# SoundLab.net
KiCad netlist of a schematic drawn in EAGLE
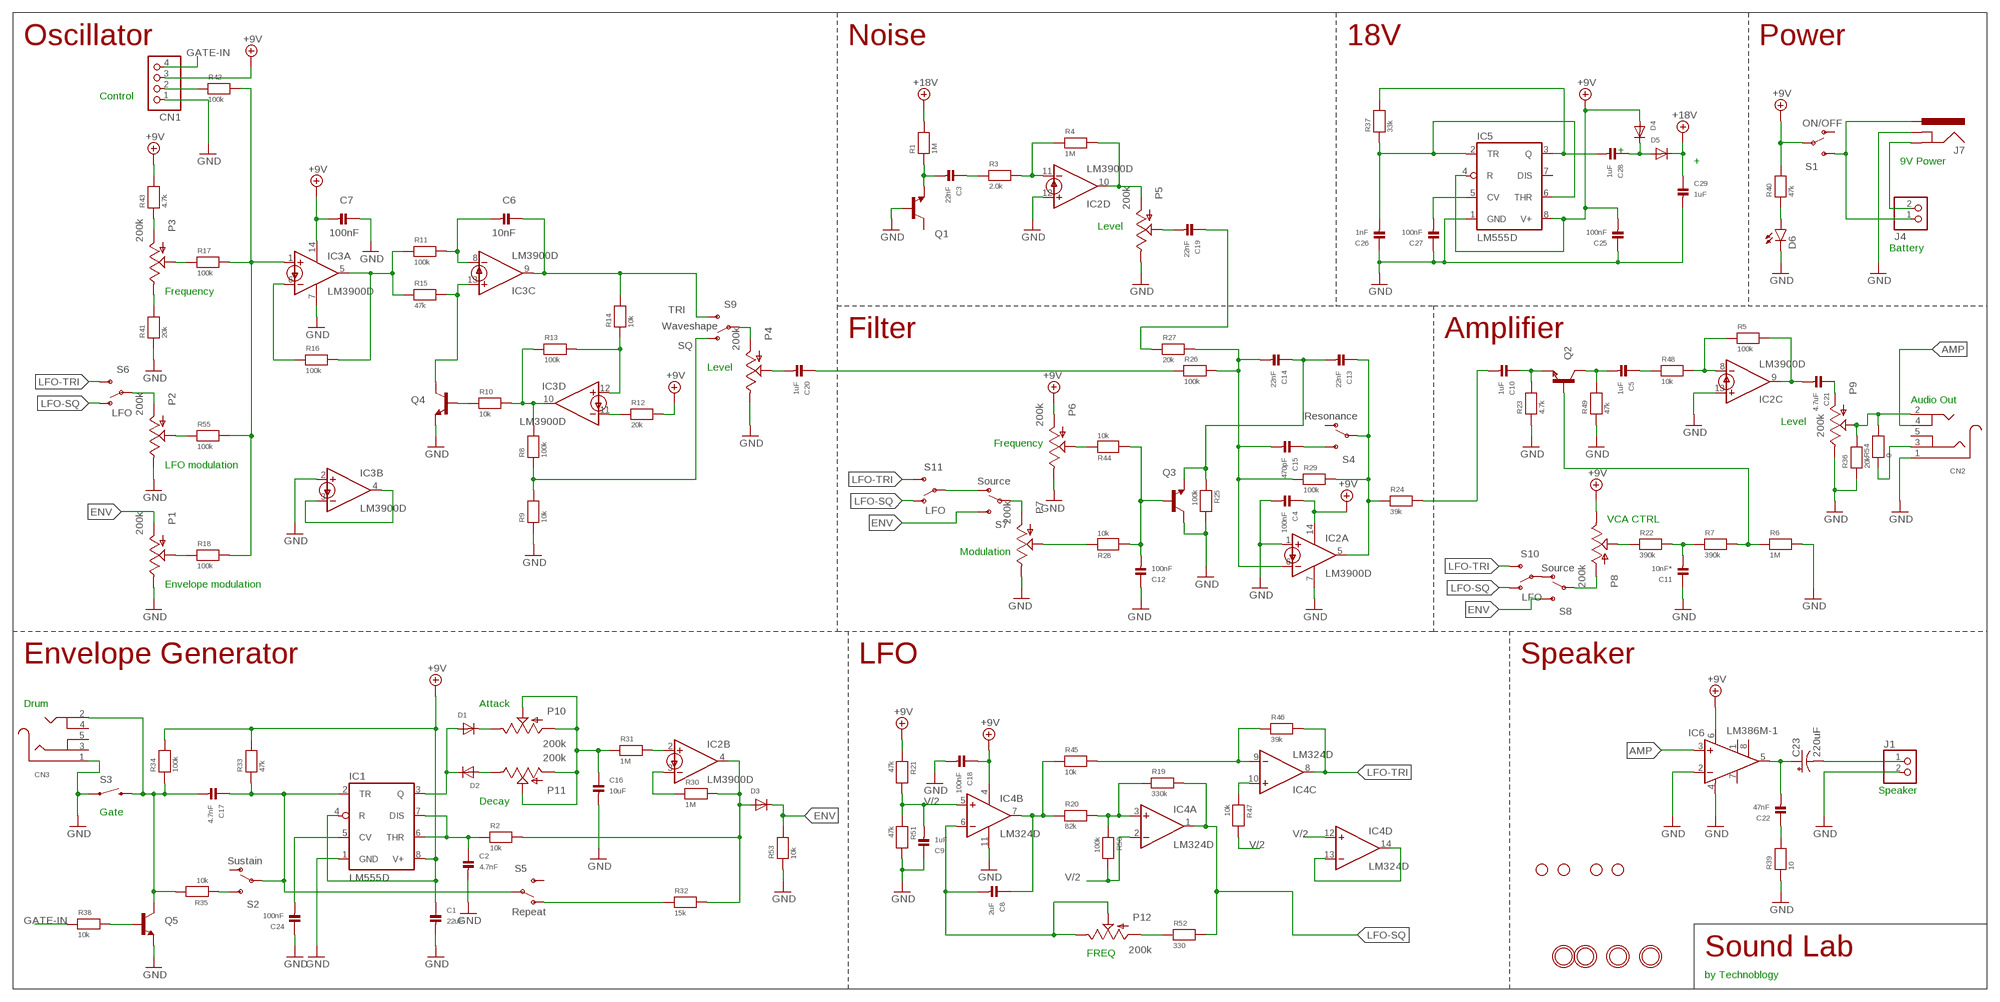
[diagram p0: schematic, sheet 1]

(export (version "E")
  (design (tool "Eeschema 10.0.6"))
  (components
    (comp (ref "C1")
      (value "22uF")
      (footprint "eagle-import:_0805MP")
      (libsource (lib "eagle-import") (part "CAP_CERAMIC_0805MP"))
    )
    (comp (ref "C2")
      (value "4.7nF")
      (footprint "eagle-import:_0805MP")
      (libsource (lib "eagle-import") (part "CAP_CERAMIC_0805MP"))
    )
    (comp (ref "C3")
      (value "22nF")
      (footprint "eagle-import:_0805MP")
      (libsource (lib "eagle-import") (part "CAP_CERAMIC_0805MP"))
    )
    (comp (ref "C4")
      (value "100nF")
      (footprint "eagle-import:_0805MP")
      (libsource (lib "eagle-import") (part "CAP_CERAMIC_0805MP"))
    )
    (comp (ref "C5")
      (value "1uF")
      (footprint "eagle-import:_0805MP")
      (libsource (lib "eagle-import") (part "CAP_CERAMIC_0805MP"))
    )
    (comp (ref "C6")
      (value "10nF")
      (footprint "eagle-import:_0805MP")
      (libsource (lib "eagle-import") (part "CAP_CERAMIC_0805MP"))
    )
    (comp (ref "C7")
      (value "100nF")
      (footprint "eagle-import:_0805MP")
      (libsource (lib "eagle-import") (part "CAP_CERAMIC_0805MP"))
    )
    (comp (ref "C8")
      (value "2uF")
      (footprint "eagle-import:_0805MP")
      (libsource (lib "eagle-import") (part "CAP_CERAMIC_0805MP"))
    )
    (comp (ref "C9")
      (value "1uF")
      (footprint "eagle-import:_0805MP")
      (libsource (lib "eagle-import") (part "CAP_CERAMIC_0805MP"))
    )
    (comp (ref "C10")
      (value "1uF")
      (footprint "eagle-import:_0805MP")
      (libsource (lib "eagle-import") (part "CAP_CERAMIC_0805MP"))
    )
    (comp (ref "C11")
      (value "10nF*")
      (footprint "eagle-import:_0805MP")
      (libsource (lib "eagle-import") (part "CAP_CERAMIC_0805MP"))
    )
    (comp (ref "C12")
      (value "100nF")
      (footprint "eagle-import:_0805MP")
      (libsource (lib "eagle-import") (part "CAP_CERAMIC_0805MP"))
    )
    (comp (ref "C13")
      (value "22nF")
      (footprint "eagle-import:_0805MP")
      (libsource (lib "eagle-import") (part "CAP_CERAMIC_0805MP"))
    )
    (comp (ref "C14")
      (value "22nF")
      (footprint "eagle-import:_0805MP")
      (libsource (lib "eagle-import") (part "CAP_CERAMIC_0805MP"))
    )
    (comp (ref "C15")
      (value "470pF")
      (footprint "eagle-import:_0805MP")
      (libsource (lib "eagle-import") (part "CAP_CERAMIC_0805MP"))
    )
    (comp (ref "C16")
      (value "10uF")
      (footprint "eagle-import:_0805MP")
      (libsource (lib "eagle-import") (part "CAP_CERAMIC_0805MP"))
    )
    (comp (ref "C17")
      (value "4.7nF")
      (footprint "eagle-import:_0805MP")
      (libsource (lib "eagle-import") (part "CAP_CERAMIC_0805MP"))
    )
    (comp (ref "C18")
      (value "100nF")
      (footprint "eagle-import:_0805MP")
      (libsource (lib "eagle-import") (part "CAP_CERAMIC_0805MP"))
    )
    (comp (ref "C19")
      (value "22nF")
      (footprint "eagle-import:_0805MP")
      (libsource (lib "eagle-import") (part "CAP_CERAMIC_0805MP"))
    )
    (comp (ref "C20")
      (value "1uF")
      (footprint "eagle-import:_0805MP")
      (libsource (lib "eagle-import") (part "CAP_CERAMIC_0805MP"))
    )
    (comp (ref "C21")
      (value "4.7uF")
      (footprint "eagle-import:_0805MP")
      (libsource (lib "eagle-import") (part "CAP_CERAMIC_0805MP"))
    )
    (comp (ref "C22")
      (value "47nF")
      (footprint "eagle-import:_0805MP")
      (libsource (lib "eagle-import") (part "CAP_CERAMIC_0805MP"))
    )
    (comp (ref "C23")
      (value "220uF")
      (footprint "eagle-import:PANASONIC_D")
      (libsource (lib "eagle-import") (part "47UF-50V-20%(ELECT)"))
    )
    (comp (ref "C24")
      (value "100nF")
      (footprint "eagle-import:_0805MP")
      (libsource (lib "eagle-import") (part "CAP_CERAMIC_0805MP"))
    )
    (comp (ref "C25")
      (value "100nF")
      (footprint "eagle-import:_0805MP")
      (libsource (lib "eagle-import") (part "CAP_CERAMIC_0805MP"))
    )
    (comp (ref "C26")
      (value "1nF")
      (footprint "eagle-import:_0805MP")
      (libsource (lib "eagle-import") (part "CAP_CERAMIC_0805MP"))
    )
    (comp (ref "C27")
      (value "100nF")
      (footprint "eagle-import:_0805MP")
      (libsource (lib "eagle-import") (part "CAP_CERAMIC_0805MP"))
    )
    (comp (ref "C28")
      (value "1uF")
      (footprint "eagle-import:_0805MP")
      (libsource (lib "eagle-import") (part "CAP_CERAMIC_0805MP"))
    )
    (comp (ref "C29")
      (value "1uF")
      (footprint "eagle-import:_0805MP")
      (libsource (lib "eagle-import") (part "CAP_CERAMIC_0805MP"))
    )
    (comp (ref "CN1")
      (value "JST_4PIN")
      (footprint "eagle-import:JSTPH4")
      (libsource (lib "eagle-import") (part "JST_4PIN"))
    )
    (comp (ref "CN2")
      (value "AUDIO_3.5MMJACK")
      (footprint "eagle-import:4UCONN_19269")
      (libsource (lib "eagle-import") (part "AUDIO_3.5MMJACK"))
    )
    (comp (ref "CN3")
      (value "AUDIO_3.5MMJACK")
      (footprint "eagle-import:4UCONN_19269")
      (libsource (lib "eagle-import") (part "AUDIO_3.5MMJACK"))
    )
    (comp (ref "D1")
      (value "DIODESOD-123")
      (footprint "eagle-import:SOD-123")
      (libsource (lib "eagle-import") (part "DIODESOD-123"))
    )
    (comp (ref "D2")
      (value "DIODESOD-123")
      (footprint "eagle-import:SOD-123")
      (libsource (lib "eagle-import") (part "DIODESOD-123"))
    )
    (comp (ref "D3")
      (value "DIODESOD-123")
      (footprint "eagle-import:SOD-123")
      (libsource (lib "eagle-import") (part "DIODESOD-123"))
    )
    (comp (ref "D4")
      (value "DIODESOD-123")
      (footprint "eagle-import:SOD-123")
      (libsource (lib "eagle-import") (part "DIODESOD-123"))
    )
    (comp (ref "D5")
      (value "DIODESOD-123")
      (footprint "eagle-import:SOD-123")
      (libsource (lib "eagle-import") (part "DIODESOD-123"))
    )
    (comp (ref "D6")
      (value "LED1206-BOTTOM")
      (footprint "eagle-import:LED-1206-BOTTOM")
      (libsource (lib "eagle-import") (part "LED1206-BOTTOM"))
    )
    (comp (ref "IC1")
      (value "LM555D")
      (footprint "eagle-import:SO08")
      (libsource (lib "eagle-import") (part "555DLM"))
    )
    (comp (ref "IC2")
      (value "LM3900D")
      (footprint "eagle-import:SO14")
      (libsource (lib "eagle-import") (part "LM3900D"))
    )
    (comp (ref "IC3")
      (value "LM3900D")
      (footprint "eagle-import:SO14")
      (libsource (lib "eagle-import") (part "LM3900D"))
    )
    (comp (ref "IC4")
      (value "LM324D")
      (footprint "eagle-import:SO14")
      (libsource (lib "eagle-import") (part "LM324D"))
    )
    (comp (ref "IC5")
      (value "LM555D")
      (footprint "eagle-import:SO08")
      (libsource (lib "eagle-import") (part "555DLM"))
    )
    (comp (ref "IC6")
      (value "LM386M-1")
      (footprint "eagle-import:SO08")
      (libsource (lib "eagle-import") (part "LM386?-M1"))
    )
    (comp (ref "J1")
      (value "HEADER-1X2EDGE")
      (footprint "eagle-import:1X02_EDGESMT")
      (libsource (lib "eagle-import") (part "HEADER-1X2EDGE"))
    )
    (comp (ref "J4")
      (value "HEADER-1X2EDGE")
      (footprint "eagle-import:1X02_EDGESMT")
      (libsource (lib "eagle-import") (part "HEADER-1X2EDGE"))
    )
    (comp (ref "J7")
      (value "5.5x2.1mm Barrel")
      (footprint "eagle-import:POWER_JACK_SMD")
      (libsource (lib "eagle-import") (part "POWER_JACKSMD"))
    )
    (comp (ref "JP1")
      (value "STAND-OFF")
      (footprint "eagle-import:STAND-OFF")
      (libsource (lib "eagle-import") (part "STAND-OFF"))
    )
    (comp (ref "JP2")
      (value "STAND-OFF")
      (footprint "eagle-import:STAND-OFF")
      (libsource (lib "eagle-import") (part "STAND-OFF"))
    )
    (comp (ref "JP3")
      (value "STAND-OFF")
      (footprint "eagle-import:STAND-OFF")
      (libsource (lib "eagle-import") (part "STAND-OFF"))
    )
    (comp (ref "JP4")
      (value "STAND-OFF")
      (footprint "eagle-import:STAND-OFF")
      (libsource (lib "eagle-import") (part "STAND-OFF"))
    )
    (comp (ref "P1")
      (value "200k")
      (footprint "eagle-import:ALPS_POT")
      (libsource (lib "eagle-import") (part "POT"))
    )
    (comp (ref "P2")
      (value "200k")
      (footprint "eagle-import:ALPS_POT")
      (libsource (lib "eagle-import") (part "POT"))
    )
    (comp (ref "P3")
      (value "200k")
      (footprint "eagle-import:ALPS_POT")
      (libsource (lib "eagle-import") (part "POT"))
    )
    (comp (ref "P4")
      (value "200k")
      (footprint "eagle-import:ALPS_POT")
      (libsource (lib "eagle-import") (part "POT"))
    )
    (comp (ref "P5")
      (value "200k")
      (footprint "eagle-import:ALPS_POT")
      (libsource (lib "eagle-import") (part "POT"))
    )
    (comp (ref "P6")
      (value "200k")
      (footprint "eagle-import:ALPS_POT")
      (libsource (lib "eagle-import") (part "POT"))
    )
    (comp (ref "P7")
      (value "200k")
      (footprint "eagle-import:ALPS_POT")
      (libsource (lib "eagle-import") (part "POT"))
    )
    (comp (ref "P8")
      (value "200k")
      (footprint "eagle-import:ALPS_POT")
      (libsource (lib "eagle-import") (part "POT"))
    )
    (comp (ref "P9")
      (value "200k")
      (footprint "eagle-import:ALPS_POT")
      (libsource (lib "eagle-import") (part "POT"))
    )
    (comp (ref "P10")
      (value "200k")
      (footprint "eagle-import:ALPS_POT")
      (libsource (lib "eagle-import") (part "POT"))
    )
    (comp (ref "P11")
      (value "200k")
      (footprint "eagle-import:ALPS_POT")
      (libsource (lib "eagle-import") (part "POT"))
    )
    (comp (ref "P12")
      (value "200k")
      (footprint "eagle-import:ALPS_POT")
      (libsource (lib "eagle-import") (part "POT"))
    )
    (comp (ref "Q1")
      (value "MMBT3904")
      (footprint "eagle-import:SOT23-3")
      (libsource (lib "eagle-import") (part "TRANSISTOR_NPNMMBT2222A"))
    )
    (comp (ref "Q2")
      (value "MMBT3904")
      (footprint "eagle-import:SOT23-3")
      (libsource (lib "eagle-import") (part "TRANSISTOR_NPNMMBT2222A"))
    )
    (comp (ref "Q3")
      (value "MMBT3904")
      (footprint "eagle-import:SOT23-3")
      (libsource (lib "eagle-import") (part "TRANSISTOR_NPNMMBT2222A"))
    )
    (comp (ref "Q4")
      (value "MMBT3904")
      (footprint "eagle-import:SOT23-3")
      (libsource (lib "eagle-import") (part "TRANSISTOR_NPNMMBT2222A"))
    )
    (comp (ref "Q5")
      (value "MMBT3904")
      (footprint "eagle-import:SOT23-3")
      (libsource (lib "eagle-import") (part "TRANSISTOR_NPNMMBT2222A"))
    )
    (comp (ref "R1")
      (value "1M")
      (footprint "eagle-import:_0805MP")
      (libsource (lib "eagle-import") (part "RESISTOR_0805MP"))
    )
    (comp (ref "R2")
      (value "10k")
      (footprint "eagle-import:_0805MP")
      (libsource (lib "eagle-import") (part "RESISTOR_0805MP"))
    )
    (comp (ref "R3")
      (value "2.0k")
      (footprint "eagle-import:_0805MP")
      (libsource (lib "eagle-import") (part "RESISTOR_0805MP"))
    )
    (comp (ref "R4")
      (value "1M")
      (footprint "eagle-import:_0805MP")
      (libsource (lib "eagle-import") (part "RESISTOR_0805MP"))
    )
    (comp (ref "R5")
      (value "100k")
      (footprint "eagle-import:_0805MP")
      (libsource (lib "eagle-import") (part "RESISTOR_0805MP"))
    )
    (comp (ref "R6")
      (value "1M")
      (footprint "eagle-import:_0805MP")
      (libsource (lib "eagle-import") (part "RESISTOR_0805MP"))
    )
    (comp (ref "R7")
      (value "390k")
      (footprint "eagle-import:_0805MP")
      (libsource (lib "eagle-import") (part "RESISTOR_0805MP"))
    )
    (comp (ref "R8")
      (value "100k")
      (footprint "eagle-import:_0805MP")
      (libsource (lib "eagle-import") (part "RESISTOR_0805MP"))
    )
    (comp (ref "R9")
      (value "10k")
      (footprint "eagle-import:_0805MP")
      (libsource (lib "eagle-import") (part "RESISTOR_0805MP"))
    )
    (comp (ref "R10")
      (value "10k")
      (footprint "eagle-import:_0805MP")
      (libsource (lib "eagle-import") (part "RESISTOR_0805MP"))
    )
    (comp (ref "R11")
      (value "100k")
      (footprint "eagle-import:_0805MP")
      (libsource (lib "eagle-import") (part "RESISTOR_0805MP"))
    )
    (comp (ref "R12")
      (value "20k")
      (footprint "eagle-import:_0805MP")
      (libsource (lib "eagle-import") (part "RESISTOR_0805MP"))
    )
    (comp (ref "R13")
      (value "100k")
      (footprint "eagle-import:_0805MP")
      (libsource (lib "eagle-import") (part "RESISTOR_0805MP"))
    )
    (comp (ref "R14")
      (value "10k")
      (footprint "eagle-import:_0805MP")
      (libsource (lib "eagle-import") (part "RESISTOR_0805MP"))
    )
    (comp (ref "R15")
      (value "47k")
      (footprint "eagle-import:_0805MP")
      (libsource (lib "eagle-import") (part "RESISTOR_0805MP"))
    )
    (comp (ref "R16")
      (value "100k")
      (footprint "eagle-import:_0805MP")
      (libsource (lib "eagle-import") (part "RESISTOR_0805MP"))
    )
    (comp (ref "R17")
      (value "100k")
      (footprint "eagle-import:_0805MP")
      (libsource (lib "eagle-import") (part "RESISTOR_0805MP"))
    )
    (comp (ref "R18")
      (value "100k")
      (footprint "eagle-import:_0805MP")
      (libsource (lib "eagle-import") (part "RESISTOR_0805MP"))
    )
    (comp (ref "R19")
      (value "330k")
      (footprint "eagle-import:_0805MP")
      (libsource (lib "eagle-import") (part "RESISTOR_0805MP"))
    )
    (comp (ref "R20")
      (value "82k")
      (footprint "eagle-import:_0805MP")
      (libsource (lib "eagle-import") (part "RESISTOR_0805MP"))
    )
    (comp (ref "R21")
      (value "47k")
      (footprint "eagle-import:_0805MP")
      (libsource (lib "eagle-import") (part "RESISTOR_0805MP"))
    )
    (comp (ref "R22")
      (value "390k")
      (footprint "eagle-import:_0805MP")
      (libsource (lib "eagle-import") (part "RESISTOR_0805MP"))
    )
    (comp (ref "R23")
      (value "4.7k")
      (footprint "eagle-import:_0805MP")
      (libsource (lib "eagle-import") (part "RESISTOR_0805MP"))
    )
    (comp (ref "R24")
      (value "39k")
      (footprint "eagle-import:_0805MP")
      (libsource (lib "eagle-import") (part "RESISTOR_0805MP"))
    )
    (comp (ref "R25")
      (value "100k")
      (footprint "eagle-import:_0805MP")
      (libsource (lib "eagle-import") (part "RESISTOR_0805MP"))
    )
    (comp (ref "R26")
      (value "100k")
      (footprint "eagle-import:_0805MP")
      (libsource (lib "eagle-import") (part "RESISTOR_0805MP"))
    )
    (comp (ref "R27")
      (value "20k")
      (footprint "eagle-import:_0805MP")
      (libsource (lib "eagle-import") (part "RESISTOR_0805MP"))
    )
    (comp (ref "R28")
      (value "10k")
      (footprint "eagle-import:_0805MP")
      (libsource (lib "eagle-import") (part "RESISTOR_0805MP"))
    )
    (comp (ref "R29")
      (value "100k")
      (footprint "eagle-import:_0805MP")
      (libsource (lib "eagle-import") (part "RESISTOR_0805MP"))
    )
    (comp (ref "R30")
      (value "1M")
      (footprint "eagle-import:_0805MP")
      (libsource (lib "eagle-import") (part "RESISTOR_0805MP"))
    )
    (comp (ref "R31")
      (value "1M")
      (footprint "eagle-import:_0805MP")
      (libsource (lib "eagle-import") (part "RESISTOR_0805MP"))
    )
    (comp (ref "R32")
      (value "15k")
      (footprint "eagle-import:_0805MP")
      (libsource (lib "eagle-import") (part "RESISTOR_0805MP"))
    )
    (comp (ref "R33")
      (value "47k")
      (footprint "eagle-import:_0805MP")
      (libsource (lib "eagle-import") (part "RESISTOR_0805MP"))
    )
    (comp (ref "R34")
      (value "100k")
      (footprint "eagle-import:_0805MP")
      (libsource (lib "eagle-import") (part "RESISTOR_0805MP"))
    )
    (comp (ref "R35")
      (value "10k")
      (footprint "eagle-import:_0805MP")
      (libsource (lib "eagle-import") (part "RESISTOR_0805MP"))
    )
    (comp (ref "R36")
      (value "20k")
      (footprint "eagle-import:_0805MP")
      (libsource (lib "eagle-import") (part "RESISTOR_0805MP"))
    )
    (comp (ref "R37")
      (value "33k")
      (footprint "eagle-import:_0805MP")
      (libsource (lib "eagle-import") (part "RESISTOR_0805MP"))
    )
    (comp (ref "R38")
      (value "10k")
      (footprint "eagle-import:_0805MP")
      (libsource (lib "eagle-import") (part "RESISTOR_0805MP"))
    )
    (comp (ref "R39")
      (value "10")
      (footprint "eagle-import:_0805MP")
      (libsource (lib "eagle-import") (part "RESISTOR_0805MP"))
    )
    (comp (ref "R40")
      (value "47k")
      (footprint "eagle-import:_0805MP")
      (libsource (lib "eagle-import") (part "RESISTOR_0805MP"))
    )
    (comp (ref "R41")
      (value "20k")
      (footprint "eagle-import:_0805MP")
      (libsource (lib "eagle-import") (part "RESISTOR_0805MP"))
    )
    (comp (ref "R42")
      (value "100k")
      (footprint "eagle-import:_0805MP")
      (libsource (lib "eagle-import") (part "RESISTOR_0805MP"))
    )
    (comp (ref "R43")
      (value "4.7k")
      (footprint "eagle-import:_0805MP")
      (libsource (lib "eagle-import") (part "RESISTOR_0805MP"))
    )
    (comp (ref "R44")
      (value "10k")
      (footprint "eagle-import:_0805MP")
      (libsource (lib "eagle-import") (part "RESISTOR_0805MP"))
    )
    (comp (ref "R45")
      (value "10k")
      (footprint "eagle-import:_0805MP")
      (libsource (lib "eagle-import") (part "RESISTOR_0805MP"))
    )
    (comp (ref "R46")
      (value "39k")
      (footprint "eagle-import:_0805MP")
      (libsource (lib "eagle-import") (part "RESISTOR_0805MP"))
    )
    (comp (ref "R47")
      (value "10k")
      (footprint "eagle-import:_0805MP")
      (libsource (lib "eagle-import") (part "RESISTOR_0805MP"))
    )
    (comp (ref "R48")
      (value "10k")
      (footprint "eagle-import:_0805MP")
      (libsource (lib "eagle-import") (part "RESISTOR_0805MP"))
    )
    (comp (ref "R49")
      (value "47k")
      (footprint "eagle-import:_0805MP")
      (libsource (lib "eagle-import") (part "RESISTOR_0805MP"))
    )
    (comp (ref "R50")
      (value "100k")
      (footprint "eagle-import:_0805MP")
      (libsource (lib "eagle-import") (part "RESISTOR_0805MP"))
    )
    (comp (ref "R51")
      (value "47k")
      (footprint "eagle-import:_0805MP")
      (libsource (lib "eagle-import") (part "RESISTOR_0805MP"))
    )
    (comp (ref "R52")
      (value "330")
      (footprint "eagle-import:_0805MP")
      (libsource (lib "eagle-import") (part "RESISTOR_0805MP"))
    )
    (comp (ref "R53")
      (value "10k")
      (footprint "eagle-import:_0805MP")
      (libsource (lib "eagle-import") (part "RESISTOR_0805MP"))
    )
    (comp (ref "R54")
      (value "0")
      (footprint "eagle-import:_0805MP")
      (libsource (lib "eagle-import") (part "RESISTOR_0805MP"))
    )
    (comp (ref "R55")
      (value "100k")
      (footprint "eagle-import:_0805MP")
      (libsource (lib "eagle-import") (part "RESISTOR_0805MP"))
    )
    (comp (ref "S1")
      (value "ON/OFF")
      (footprint "eagle-import:SWITCH-SPDT")
      (libsource (lib "eagle-import") (part "SWITCH-SPDTPTH"))
    )
    (comp (ref "S2")
      (value "Sustain")
      (footprint "eagle-import:SWITCH-SPDT")
      (libsource (lib "eagle-import") (part "SWITCH-SPDTPTH"))
    )
    (comp (ref "S3")
      (value "SWITCH-MOMENTARY-212MM")
      (footprint "eagle-import:TACTILE-PTH-12MM")
      (libsource (lib "eagle-import") (part "SWITCH-MOMENTARY-212MM"))
    )
    (comp (ref "S4")
      (value "Resonance")
      (footprint "eagle-import:SWITCH-SPDT")
      (libsource (lib "eagle-import") (part "SWITCH-SPDTPTH"))
    )
    (comp (ref "S5")
      (value "Repeat")
      (footprint "eagle-import:SWITCH-SPDT")
      (libsource (lib "eagle-import") (part "SWITCH-SPDTPTH"))
    )
    (comp (ref "S6")
      (value "LFO")
      (footprint "eagle-import:SWITCH-SPDT")
      (libsource (lib "eagle-import") (part "SWITCH-SPDTPTH"))
    )
    (comp (ref "S7")
      (value "Source")
      (footprint "eagle-import:SWITCH-SPDT")
      (libsource (lib "eagle-import") (part "SWITCH-SPDTPTH"))
    )
    (comp (ref "S8")
      (value "Source")
      (footprint "eagle-import:SWITCH-SPDT")
      (libsource (lib "eagle-import") (part "SWITCH-SPDTPTH"))
    )
    (comp (ref "S9")
      (value "Waveshape")
      (footprint "eagle-import:SWITCH-SPDT")
      (libsource (lib "eagle-import") (part "SWITCH-SPDTPTH"))
    )
    (comp (ref "S10")
      (value "LFO")
      (footprint "eagle-import:SWITCH-SPDT")
      (libsource (lib "eagle-import") (part "SWITCH-SPDTPTH"))
    )
    (comp (ref "S11")
      (value "LFO")
      (footprint "eagle-import:SWITCH-SPDT")
      (libsource (lib "eagle-import") (part "SWITCH-SPDTPTH"))
    )
    (comp (ref "U$2")
      (value "MOUNTINGHOLE2.0")
      (footprint "eagle-import:MOUNTINGHOLE_2.0_PLATED")
      (libsource (lib "eagle-import") (part "MOUNTINGHOLE2.0"))
    )
    (comp (ref "U$3")
      (value "MOUNTINGHOLE2.0")
      (footprint "eagle-import:MOUNTINGHOLE_2.0_PLATED")
      (libsource (lib "eagle-import") (part "MOUNTINGHOLE2.0"))
    )
    (comp (ref "U$6")
      (value "MOUNTINGHOLE2.0")
      (footprint "eagle-import:MOUNTINGHOLE_2.0_PLATED")
      (libsource (lib "eagle-import") (part "MOUNTINGHOLE2.0"))
    )
    (comp (ref "U$7")
      (value "MOUNTINGHOLE2.0")
      (footprint "eagle-import:MOUNTINGHOLE_2.0_PLATED")
      (libsource (lib "eagle-import") (part "MOUNTINGHOLE2.0"))
    )
  )
  (nets
    (net (code "1") (name "+9V") (class "Default")
      (node (ref "C1") (pin "1") (pinfunction "P$1_1") (pintype "passive"))
      (node (ref "C18") (pin "1") (pinfunction "P$1_1") (pintype "passive"))
      (node (ref "C25") (pin "2") (pinfunction "P$2_2") (pintype "passive"))
      (node (ref "C4") (pin "1") (pinfunction "P$1_1") (pintype "passive"))
      (node (ref "C7") (pin "2") (pinfunction "P$2_2") (pintype "passive"))
      (node (ref "CN1") (pin "3") (pinfunction "3_3") (pintype "passive"))
      (node (ref "D4") (pin "A") (pinfunction "A_A") (pintype "passive"))
      (node (ref "IC1") (pin "4") (pinfunction "R_4") (pintype "input"))
      (node (ref "IC1") (pin "8") (pinfunction "V+_8") (pintype "power_in"))
      (node (ref "IC2") (pin "14") (pinfunction "V+_14") (pintype "power_in"))
      (node (ref "IC3") (pin "14") (pinfunction "V+_14") (pintype "power_in"))
      (node (ref "IC4") (pin "4") (pinfunction "V+_4") (pintype "power_in"))
      (node (ref "IC5") (pin "4") (pinfunction "R_4") (pintype "input"))
      (node (ref "IC5") (pin "8") (pinfunction "V+_8") (pintype "power_in"))
      (node (ref "IC6") (pin "6") (pinfunction "VS_6") (pintype "power_in"))
      (node (ref "P6") (pin "P$3") (pinfunction "A_P$3") (pintype "passive"))
      (node (ref "P8") (pin "P$1") (pinfunction "E_P$1") (pintype "passive"))
      (node (ref "R12") (pin "2") (pinfunction "2_2") (pintype "passive"))
      (node (ref "R21") (pin "1") (pinfunction "1_1") (pintype "passive"))
      (node (ref "R33") (pin "2") (pinfunction "2_2") (pintype "passive"))
      (node (ref "R34") (pin "2") (pinfunction "2_2") (pintype "passive"))
      (node (ref "R40") (pin "2") (pinfunction "2_2") (pintype "passive"))
      (node (ref "R43") (pin "2") (pinfunction "2_2") (pintype "passive"))
      (node (ref "S1") (pin "2") (pinfunction "P_2") (pintype "passive"))
    )
    (net (code "2") (name "+18V") (class "Default")
      (node (ref "C29") (pin "1") (pinfunction "P$1_1") (pintype "passive"))
      (node (ref "D5") (pin "C") (pinfunction "C_C") (pintype "passive"))
      (node (ref "R1") (pin "2") (pinfunction "2_2") (pintype "passive"))
    )
    (net (code "3") (name "/GATE-IN") (class "Default")
      (node (ref "CN1") (pin "4") (pinfunction "4_4") (pintype "passive"))
      (node (ref "R38") (pin "1") (pinfunction "1_1") (pintype "passive"))
    )
    (net (code "4") (name "/SQ") (class "Default")
      (node (ref "R8") (pin "1") (pinfunction "1_1") (pintype "passive"))
      (node (ref "R9") (pin "2") (pinfunction "2_2") (pintype "passive"))
      (node (ref "S9") (pin "1") (pinfunction "O_1") (pintype "passive"))
    )
    (net (code "5") (name "/TRI") (class "Default")
      (node (ref "C6") (pin "1") (pinfunction "P$1_1") (pintype "passive"))
      (node (ref "IC3") (pin "9") (pinfunction "OUT_9") (pintype "output"))
      (node (ref "R14") (pin "2") (pinfunction "2_2") (pintype "passive"))
      (node (ref "S9") (pin "3") (pinfunction "S_3") (pintype "passive"))
    )
    (net (code "6") (name "/V{slash}2") (class "Default")
      (node (ref "C9") (pin "2") (pinfunction "P$2_2") (pintype "passive"))
      (node (ref "IC4") (pin "12") (pinfunction "+IN_12") (pintype "input"))
      (node (ref "IC4") (pin "2") (pinfunction "-IN_2") (pintype "input"))
      (node (ref "IC4") (pin "5") (pinfunction "+IN_5") (pintype "input"))
      (node (ref "R21") (pin "2") (pinfunction "2_2") (pintype "passive"))
      (node (ref "R47") (pin "2") (pinfunction "2_2") (pintype "passive"))
      (node (ref "R50") (pin "2") (pinfunction "2_2") (pintype "passive"))
      (node (ref "R51") (pin "1") (pinfunction "1_1") (pintype "passive"))
    )
    (net (code "7") (name "AMP") (class "Default")
      (node (ref "CN2") (pin "4") (pinfunction "P$4_4") (pintype "bidirectional"))
      (node (ref "IC6") (pin "3") (pinfunction "+IN_3") (pintype "input"))
    )
    (net (code "8") (name "ENV") (class "Default")
      (node (ref "D3") (pin "C") (pinfunction "C_C") (pintype "passive"))
      (node (ref "P1") (pin "P$3") (pinfunction "A_P$3") (pintype "passive"))
      (node (ref "R53") (pin "2") (pinfunction "2_2") (pintype "passive"))
      (node (ref "S7") (pin "3") (pinfunction "S_3") (pintype "passive"))
      (node (ref "S8") (pin "3") (pinfunction "S_3") (pintype "passive"))
    )
    (net (code "9") (name "GND") (class "Default")
      (node (ref "C1") (pin "2") (pinfunction "P$2_2") (pintype "passive"))
      (node (ref "C11") (pin "1") (pinfunction "P$1_1") (pintype "passive"))
      (node (ref "C12") (pin "1") (pinfunction "P$1_1") (pintype "passive"))
      (node (ref "C16") (pin "2") (pinfunction "P$2_2") (pintype "passive"))
      (node (ref "C18") (pin "2") (pinfunction "P$2_2") (pintype "passive"))
      (node (ref "C2") (pin "2") (pinfunction "P$2_2") (pintype "passive"))
      (node (ref "C24") (pin "1") (pinfunction "P$1_1") (pintype "passive"))
      (node (ref "C25") (pin "1") (pinfunction "P$1_1") (pintype "passive"))
      (node (ref "C26") (pin "1") (pinfunction "P$1_1") (pintype "passive"))
      (node (ref "C27") (pin "1") (pinfunction "P$1_1") (pintype "passive"))
      (node (ref "C29") (pin "2") (pinfunction "P$2_2") (pintype "passive"))
      (node (ref "C4") (pin "2") (pinfunction "P$2_2") (pintype "passive"))
      (node (ref "C7") (pin "1") (pinfunction "P$1_1") (pintype "passive"))
      (node (ref "C9") (pin "1") (pinfunction "P$1_1") (pintype "passive"))
      (node (ref "CN1") (pin "1") (pinfunction "1_1") (pintype "passive"))
      (node (ref "CN2") (pin "1") (pinfunction "P$1_1") (pintype "bidirectional"))
      (node (ref "CN3") (pin "1") (pinfunction "P$1_1") (pintype "bidirectional"))
      (node (ref "D6") (pin "C") (pinfunction "C_C") (pintype "passive"))
      (node (ref "IC1") (pin "1") (pinfunction "GND_1") (pintype "power_in"))
      (node (ref "IC2") (pin "1") (pinfunction "+IN_1") (pintype "input"))
      (node (ref "IC2") (pin "12") (pinfunction "+IN_12") (pintype "input"))
      (node (ref "IC2") (pin "13") (pinfunction "+IN_13") (pintype "input"))
      (node (ref "IC2") (pin "7") (pinfunction "GND_7") (pintype "power_in"))
      (node (ref "IC3") (pin "2") (pinfunction "+IN_2") (pintype "input"))
      (node (ref "IC3") (pin "7") (pinfunction "GND_7") (pintype "power_in"))
      (node (ref "IC4") (pin "11") (pinfunction "V-_11") (pintype "power_in"))
      (node (ref "IC5") (pin "1") (pinfunction "GND_1") (pintype "power_in"))
      (node (ref "IC6") (pin "2") (pinfunction "-IN_2") (pintype "input"))
      (node (ref "IC6") (pin "4") (pinfunction "GND_4") (pintype "power_in"))
      (node (ref "J1") (pin "2") (pinfunction "2_2") (pintype "passive"))
      (node (ref "J7") (pin "GND") (pinfunction "GNDBREAK_GND") (pintype "bidirectional"))
      (node (ref "P1") (pin "P$1") (pinfunction "E_P$1") (pintype "passive"))
      (node (ref "P2") (pin "P$1") (pinfunction "E_P$1") (pintype "passive"))
      (node (ref "P4") (pin "P$1") (pinfunction "E_P$1") (pintype "passive"))
      (node (ref "P5") (pin "P$1") (pinfunction "E_P$1") (pintype "passive"))
      (node (ref "P6") (pin "P$1") (pinfunction "E_P$1") (pintype "passive"))
      (node (ref "P7") (pin "P$1") (pinfunction "E_P$1") (pintype "passive"))
      (node (ref "P9") (pin "P$1") (pinfunction "E_P$1") (pintype "passive"))
      (node (ref "Q1") (pin "1") (pinfunction "B_1") (pintype "passive"))
      (node (ref "Q3") (pin "3") (pinfunction "C_3") (pintype "passive"))
      (node (ref "Q4") (pin "2") (pinfunction "E_2") (pintype "passive"))
      (node (ref "Q5") (pin "2") (pinfunction "E_2") (pintype "passive"))
      (node (ref "R23") (pin "1") (pinfunction "1_1") (pintype "passive"))
      (node (ref "R25") (pin "2") (pinfunction "2_2") (pintype "passive"))
      (node (ref "R36") (pin "1") (pinfunction "1_1") (pintype "passive"))
      (node (ref "R39") (pin "1") (pinfunction "1_1") (pintype "passive"))
      (node (ref "R41") (pin "1") (pinfunction "1_1") (pintype "passive"))
      (node (ref "R49") (pin "1") (pinfunction "1_1") (pintype "passive"))
      (node (ref "R51") (pin "2") (pinfunction "2_2") (pintype "passive"))
      (node (ref "R53") (pin "1") (pinfunction "1_1") (pintype "passive"))
      (node (ref "R6") (pin "2") (pinfunction "2_2") (pintype "passive"))
      (node (ref "R9") (pin "1") (pinfunction "1_1") (pintype "passive"))
      (node (ref "S3") (pin "1") (pinfunction "1_1") (pintype "passive"))
    )
    (net (code "10") (name "LFO-SQ") (class "Default")
      (node (ref "IC4") (pin "1") (pinfunction "OUT_1") (pintype "output"))
      (node (ref "R19") (pin "2") (pinfunction "2_2") (pintype "passive"))
      (node (ref "R52") (pin "2") (pinfunction "2_2") (pintype "passive"))
      (node (ref "S10") (pin "1") (pinfunction "O_1") (pintype "passive"))
      (node (ref "S11") (pin "1") (pinfunction "O_1") (pintype "passive"))
      (node (ref "S6") (pin "1") (pinfunction "O_1") (pintype "passive"))
    )
    (net (code "11") (name "LFO-TRI") (class "Default")
      (node (ref "IC4") (pin "8") (pinfunction "OUT_8") (pintype "output"))
      (node (ref "R46") (pin "2") (pinfunction "2_2") (pintype "passive"))
      (node (ref "S10") (pin "3") (pinfunction "S_3") (pintype "passive"))
      (node (ref "S11") (pin "3") (pinfunction "S_3") (pintype "passive"))
      (node (ref "S6") (pin "3") (pinfunction "S_3") (pintype "passive"))
    )
    (net (code "12") (name "Net-(C2-P$1)") (class "Default")
      (node (ref "C2") (pin "1") (pinfunction "P$1_1") (pintype "passive"))
      (node (ref "IC1") (pin "6") (pinfunction "THR_6") (pintype "input"))
      (node (ref "IC1") (pin "7") (pinfunction "DIS_7") (pintype "input"))
      (node (ref "R2") (pin "1") (pinfunction "1_1") (pintype "passive"))
    )
    (net (code "13") (name "Net-(C3-P$1)") (class "Default")
      (node (ref "C3") (pin "1") (pinfunction "P$1_1") (pintype "passive"))
      (node (ref "R3") (pin "1") (pinfunction "1_1") (pintype "passive"))
    )
    (net (code "14") (name "Net-(C3-P$2)") (class "Default")
      (node (ref "C3") (pin "2") (pinfunction "P$2_2") (pintype "passive"))
      (node (ref "Q1") (pin "2") (pinfunction "E_2") (pintype "passive"))
      (node (ref "R1") (pin "1") (pinfunction "1_1") (pintype "passive"))
    )
    (net (code "15") (name "Net-(C5-P$1)") (class "Default")
      (node (ref "C5") (pin "1") (pinfunction "P$1_1") (pintype "passive"))
      (node (ref "R48") (pin "1") (pinfunction "1_1") (pintype "passive"))
    )
    (net (code "16") (name "Net-(C5-P$2)") (class "Default")
      (node (ref "C5") (pin "2") (pinfunction "P$2_2") (pintype "passive"))
      (node (ref "Q2") (pin "3") (pinfunction "C_3") (pintype "passive"))
      (node (ref "R49") (pin "2") (pinfunction "2_2") (pintype "passive"))
    )
    (net (code "17") (name "Net-(C6-P$2)") (class "Default")
      (node (ref "C6") (pin "2") (pinfunction "P$2_2") (pintype "passive"))
      (node (ref "IC3") (pin "8") (pinfunction "-IN_8") (pintype "input"))
      (node (ref "R11") (pin "2") (pinfunction "2_2") (pintype "passive"))
    )
    (net (code "18") (name "Net-(C8-P$1)") (class "Default")
      (node (ref "C8") (pin "1") (pinfunction "P$1_1") (pintype "passive"))
      (node (ref "IC4") (pin "7") (pinfunction "OUT_7") (pintype "output"))
      (node (ref "R20") (pin "1") (pinfunction "1_1") (pintype "passive"))
      (node (ref "R45") (pin "1") (pinfunction "1_1") (pintype "passive"))
    )
    (net (code "19") (name "Net-(C8-P$2)") (class "Default")
      (node (ref "C8") (pin "2") (pinfunction "P$2_2") (pintype "passive"))
      (node (ref "IC4") (pin "6") (pinfunction "-IN_6") (pintype "input"))
      (node (ref "P12") (pin "P$1") (pinfunction "E_P$1") (pintype "passive"))
      (node (ref "P12") (pin "P$2") (pinfunction "S_P$2") (pintype "passive"))
    )
    (net (code "20") (name "Net-(C10-P$1)") (class "Default")
      (node (ref "C10") (pin "1") (pinfunction "P$1_1") (pintype "passive"))
      (node (ref "Q2") (pin "2") (pinfunction "E_2") (pintype "passive"))
      (node (ref "R23") (pin "2") (pinfunction "2_2") (pintype "passive"))
    )
    (net (code "21") (name "Net-(C10-P$2)") (class "Default")
      (node (ref "C10") (pin "2") (pinfunction "P$2_2") (pintype "passive"))
      (node (ref "R24") (pin "2") (pinfunction "2_2") (pintype "passive"))
    )
    (net (code "22") (name "Net-(C11-P$2)") (class "Default")
      (node (ref "C11") (pin "2") (pinfunction "P$2_2") (pintype "passive"))
      (node (ref "R22") (pin "2") (pinfunction "2_2") (pintype "passive"))
      (node (ref "R7") (pin "1") (pinfunction "1_1") (pintype "passive"))
    )
    (net (code "23") (name "Net-(C12-P$2)") (class "Default")
      (node (ref "C12") (pin "2") (pinfunction "P$2_2") (pintype "passive"))
      (node (ref "Q3") (pin "1") (pinfunction "B_1") (pintype "passive"))
      (node (ref "R28") (pin "2") (pinfunction "2_2") (pintype "passive"))
      (node (ref "R44") (pin "2") (pinfunction "2_2") (pintype "passive"))
    )
    (net (code "24") (name "Net-(C13-P$1)") (class "Default")
      (node (ref "C13") (pin "1") (pinfunction "P$1_1") (pintype "passive"))
      (node (ref "IC2") (pin "5") (pinfunction "OUT_5") (pintype "output"))
      (node (ref "R24") (pin "1") (pinfunction "1_1") (pintype "passive"))
      (node (ref "R29") (pin "2") (pinfunction "2_2") (pintype "passive"))
      (node (ref "S4") (pin "2") (pinfunction "P_2") (pintype "passive"))
    )
    (net (code "25") (name "Net-(C13-P$2)") (class "Default")
      (node (ref "C13") (pin "2") (pinfunction "P$2_2") (pintype "passive"))
      (node (ref "C14") (pin "1") (pinfunction "P$1_1") (pintype "passive"))
      (node (ref "Q3") (pin "2") (pinfunction "E_2") (pintype "passive"))
      (node (ref "R25") (pin "1") (pinfunction "1_1") (pintype "passive"))
    )
    (net (code "26") (name "Net-(C14-P$2)") (class "Default")
      (node (ref "C14") (pin "2") (pinfunction "P$2_2") (pintype "passive"))
      (node (ref "C15") (pin "2") (pinfunction "P$2_2") (pintype "passive"))
      (node (ref "IC2") (pin "6") (pinfunction "-IN_6") (pintype "input"))
      (node (ref "R26") (pin "2") (pinfunction "2_2") (pintype "passive"))
      (node (ref "R27") (pin "2") (pinfunction "2_2") (pintype "passive"))
      (node (ref "R29") (pin "1") (pinfunction "1_1") (pintype "passive"))
    )
    (net (code "27") (name "Net-(C15-P$1)") (class "Default")
      (node (ref "C15") (pin "1") (pinfunction "P$1_1") (pintype "passive"))
      (node (ref "S4") (pin "3") (pinfunction "S_3") (pintype "passive"))
    )
    (net (code "28") (name "Net-(C16-P$1)") (class "Default")
      (node (ref "C16") (pin "1") (pinfunction "P$1_1") (pintype "passive"))
      (node (ref "P10") (pin "P$2") (pinfunction "S_P$2") (pintype "passive"))
      (node (ref "P10") (pin "P$3") (pinfunction "A_P$3") (pintype "passive"))
      (node (ref "P11") (pin "P$2") (pinfunction "S_P$2") (pintype "passive"))
      (node (ref "P11") (pin "P$3") (pinfunction "A_P$3") (pintype "passive"))
      (node (ref "R31") (pin "1") (pinfunction "1_1") (pintype "passive"))
    )
    (net (code "29") (name "Net-(C17-P$1)") (class "Default")
      (node (ref "C17") (pin "1") (pinfunction "P$1_1") (pintype "passive"))
      (node (ref "IC1") (pin "2") (pinfunction "TR_2") (pintype "input"))
      (node (ref "R33") (pin "1") (pinfunction "1_1") (pintype "passive"))
      (node (ref "S2") (pin "2") (pinfunction "P_2") (pintype "passive"))
      (node (ref "S5") (pin "2") (pinfunction "P_2") (pintype "passive"))
    )
    (net (code "30") (name "Net-(C17-P$2)") (class "Default")
      (node (ref "C17") (pin "2") (pinfunction "P$2_2") (pintype "passive"))
      (node (ref "CN3") (pin "2") (pinfunction "P$5_2") (pintype "bidirectional"))
      (node (ref "Q5") (pin "3") (pinfunction "C_3") (pintype "passive"))
      (node (ref "R34") (pin "1") (pinfunction "1_1") (pintype "passive"))
      (node (ref "R35") (pin "2") (pinfunction "2_2") (pintype "passive"))
      (node (ref "S3") (pin "3") (pinfunction "2_3") (pintype "passive"))
    )
    (net (code "31") (name "Net-(C19-P$1)") (class "Default")
      (node (ref "C19") (pin "1") (pinfunction "P$1_1") (pintype "passive"))
      (node (ref "R27") (pin "1") (pinfunction "1_1") (pintype "passive"))
    )
    (net (code "32") (name "Net-(C19-P$2)") (class "Default")
      (node (ref "C19") (pin "2") (pinfunction "P$2_2") (pintype "passive"))
      (node (ref "P5") (pin "P$2") (pinfunction "S_P$2") (pintype "passive"))
    )
    (net (code "33") (name "Net-(C20-P$1)") (class "Default")
      (node (ref "C20") (pin "1") (pinfunction "P$1_1") (pintype "passive"))
      (node (ref "R26") (pin "1") (pinfunction "1_1") (pintype "passive"))
    )
    (net (code "34") (name "Net-(C20-P$2)") (class "Default")
      (node (ref "C20") (pin "2") (pinfunction "P$2_2") (pintype "passive"))
      (node (ref "P4") (pin "P$2") (pinfunction "S_P$2") (pintype "passive"))
    )
    (net (code "35") (name "Net-(C21-P$1)") (class "Default")
      (node (ref "C21") (pin "1") (pinfunction "P$1_1") (pintype "passive"))
      (node (ref "P9") (pin "P$3") (pinfunction "A_P$3") (pintype "passive"))
    )
    (net (code "36") (name "Net-(C21-P$2)") (class "Default")
      (node (ref "C21") (pin "2") (pinfunction "P$2_2") (pintype "passive"))
      (node (ref "IC2") (pin "9") (pinfunction "OUT_9") (pintype "output"))
      (node (ref "R5") (pin "2") (pinfunction "2_2") (pintype "passive"))
    )
    (net (code "37") (name "Net-(C22-P$1)") (class "Default")
      (node (ref "C22") (pin "1") (pinfunction "P$1_1") (pintype "passive"))
      (node (ref "R39") (pin "2") (pinfunction "2_2") (pintype "passive"))
    )
    (net (code "38") (name "Net-(C22-P$2)") (class "Default")
      (node (ref "C22") (pin "2") (pinfunction "P$2_2") (pintype "passive"))
      (node (ref "C23") (pin "+") (pinfunction "+_+") (pintype "passive"))
      (node (ref "IC6") (pin "5") (pinfunction "OUT_5") (pintype "output"))
    )
    (net (code "39") (name "Net-(C23-Pad-)") (class "Default")
      (node (ref "C23") (pin "-") (pinfunction "-_-") (pintype "passive"))
      (node (ref "J1") (pin "1") (pinfunction "1_1") (pintype "passive"))
    )
    (net (code "40") (name "Net-(C24-P$2)") (class "Default")
      (node (ref "C24") (pin "2") (pinfunction "P$2_2") (pintype "passive"))
      (node (ref "IC1") (pin "5") (pinfunction "CV_5") (pintype "input"))
    )
    (net (code "41") (name "Net-(C26-P$2)") (class "Default")
      (node (ref "C26") (pin "2") (pinfunction "P$2_2") (pintype "passive"))
      (node (ref "IC5") (pin "2") (pinfunction "TR_2") (pintype "input"))
      (node (ref "IC5") (pin "6") (pinfunction "THR_6") (pintype "input"))
      (node (ref "R37") (pin "1") (pinfunction "1_1") (pintype "passive"))
    )
    (net (code "42") (name "Net-(C27-P$2)") (class "Default")
      (node (ref "C27") (pin "2") (pinfunction "P$2_2") (pintype "passive"))
      (node (ref "IC5") (pin "5") (pinfunction "CV_5") (pintype "input"))
    )
    (net (code "43") (name "Net-(C28-P$1)") (class "Default")
      (node (ref "C28") (pin "1") (pinfunction "P$1_1") (pintype "passive"))
      (node (ref "D4") (pin "C") (pinfunction "C_C") (pintype "passive"))
      (node (ref "D5") (pin "A") (pinfunction "A_A") (pintype "passive"))
    )
    (net (code "44") (name "Net-(C28-P$2)") (class "Default")
      (node (ref "C28") (pin "2") (pinfunction "P$2_2") (pintype "passive"))
      (node (ref "IC5") (pin "3") (pinfunction "Q_3") (pintype "output"))
      (node (ref "R37") (pin "2") (pinfunction "2_2") (pintype "passive"))
    )
    (net (code "45") (name "Net-(CN1-Pad2)") (class "Default")
      (node (ref "CN1") (pin "2") (pinfunction "2_2") (pintype "passive"))
      (node (ref "R42") (pin "1") (pinfunction "1_1") (pintype "passive"))
    )
    (net (code "46") (name "Net-(CN2-P$2)") (class "Default")
      (node (ref "CN2") (pin "3") (pinfunction "P$2_3") (pintype "bidirectional"))
      (node (ref "R54") (pin "1") (pinfunction "1_1") (pintype "passive"))
    )
    (net (code "47") (name "Net-(CN2-P$5)") (class "Default")
      (node (ref "CN2") (pin "2") (pinfunction "P$5_2") (pintype "bidirectional"))
      (node (ref "P9") (pin "P$2") (pinfunction "S_P$2") (pintype "passive"))
      (node (ref "R36") (pin "2") (pinfunction "2_2") (pintype "passive"))
      (node (ref "R54") (pin "2") (pinfunction "2_2") (pintype "passive"))
    )
    (net (code "48") (name "Net-(D6-PadA)") (class "Default")
      (node (ref "D6") (pin "A") (pinfunction "A_A") (pintype "passive"))
      (node (ref "R40") (pin "1") (pinfunction "1_1") (pintype "passive"))
    )
    (net (code "49") (name "Net-(IC1-Q)") (class "Default")
      (node (ref "D1") (pin "A") (pinfunction "A_A") (pintype "passive"))
      (node (ref "D2") (pin "C") (pinfunction "C_C") (pintype "passive"))
      (node (ref "IC1") (pin "3") (pinfunction "Q_3") (pintype "output"))
    )
    (net (code "50") (name "Net-(IC2B-+IN)") (class "Default")
      (node (ref "IC2") (pin "2") (pinfunction "+IN_2") (pintype "input"))
      (node (ref "R31") (pin "2") (pinfunction "2_2") (pintype "passive"))
    )
    (net (code "51") (name "Net-(IC2B--IN)") (class "Default")
      (node (ref "IC2") (pin "3") (pinfunction "-IN_3") (pintype "input"))
      (node (ref "R30") (pin "1") (pinfunction "1_1") (pintype "passive"))
    )
    (net (code "52") (name "Net-(IC2B-OUT)") (class "Default")
      (node (ref "D3") (pin "A") (pinfunction "A_A") (pintype "passive"))
      (node (ref "IC2") (pin "4") (pinfunction "OUT_4") (pintype "output"))
      (node (ref "R2") (pin "2") (pinfunction "2_2") (pintype "passive"))
      (node (ref "R30") (pin "2") (pinfunction "2_2") (pintype "passive"))
      (node (ref "R32") (pin "2") (pinfunction "2_2") (pintype "passive"))
    )
    (net (code "53") (name "Net-(IC2C--IN)") (class "Default")
      (node (ref "IC2") (pin "8") (pinfunction "-IN_8") (pintype "input"))
      (node (ref "R48") (pin "2") (pinfunction "2_2") (pintype "passive"))
      (node (ref "R5") (pin "1") (pinfunction "1_1") (pintype "passive"))
    )
    (net (code "54") (name "Net-(IC2D--IN)") (class "Default")
      (node (ref "IC2") (pin "11") (pinfunction "-IN_11") (pintype "input"))
      (node (ref "R3") (pin "2") (pinfunction "2_2") (pintype "passive"))
      (node (ref "R4") (pin "1") (pinfunction "1_1") (pintype "passive"))
    )
    (net (code "55") (name "Net-(IC2D-OUT)") (class "Default")
      (node (ref "IC2") (pin "10") (pinfunction "OUT_10") (pintype "output"))
      (node (ref "P5") (pin "P$3") (pinfunction "A_P$3") (pintype "passive"))
      (node (ref "R4") (pin "2") (pinfunction "2_2") (pintype "passive"))
    )
    (net (code "56") (name "Net-(IC3A-+IN)") (class "Default")
      (node (ref "IC3") (pin "1") (pinfunction "+IN_1") (pintype "input"))
      (node (ref "R17") (pin "2") (pinfunction "2_2") (pintype "passive"))
      (node (ref "R18") (pin "2") (pinfunction "2_2") (pintype "passive"))
      (node (ref "R42") (pin "2") (pinfunction "2_2") (pintype "passive"))
      (node (ref "R55") (pin "2") (pinfunction "2_2") (pintype "passive"))
    )
    (net (code "57") (name "Net-(IC3A--IN)") (class "Default")
      (node (ref "IC3") (pin "6") (pinfunction "-IN_6") (pintype "input"))
      (node (ref "R16") (pin "1") (pinfunction "1_1") (pintype "passive"))
    )
    (net (code "58") (name "Net-(IC3A-OUT)") (class "Default")
      (node (ref "IC3") (pin "5") (pinfunction "OUT_5") (pintype "output"))
      (node (ref "R11") (pin "1") (pinfunction "1_1") (pintype "passive"))
      (node (ref "R15") (pin "1") (pinfunction "1_1") (pintype "passive"))
      (node (ref "R16") (pin "2") (pinfunction "2_2") (pintype "passive"))
    )
    (net (code "59") (name "Net-(IC3B--IN)") (class "Default")
      (node (ref "IC3") (pin "3") (pinfunction "-IN_3") (pintype "input"))
      (node (ref "IC3") (pin "4") (pinfunction "OUT_4") (pintype "output"))
    )
    (net (code "60") (name "Net-(IC3C-+IN)") (class "Default")
      (node (ref "IC3") (pin "13") (pinfunction "+IN_13") (pintype "input"))
      (node (ref "Q4") (pin "3") (pinfunction "C_3") (pintype "passive"))
      (node (ref "R15") (pin "2") (pinfunction "2_2") (pintype "passive"))
    )
    (net (code "61") (name "Net-(IC3D-+IN)") (class "Default")
      (node (ref "IC3") (pin "12") (pinfunction "+IN_12") (pintype "input"))
      (node (ref "R13") (pin "2") (pinfunction "2_2") (pintype "passive"))
      (node (ref "R14") (pin "1") (pinfunction "1_1") (pintype "passive"))
    )
    (net (code "62") (name "Net-(IC3D--IN)") (class "Default")
      (node (ref "IC3") (pin "11") (pinfunction "-IN_11") (pintype "input"))
      (node (ref "R12") (pin "1") (pinfunction "1_1") (pintype "passive"))
    )
    (net (code "63") (name "Net-(IC3D-OUT)") (class "Default")
      (node (ref "IC3") (pin "10") (pinfunction "OUT_10") (pintype "output"))
      (node (ref "R10") (pin "2") (pinfunction "2_2") (pintype "passive"))
      (node (ref "R13") (pin "1") (pinfunction "1_1") (pintype "passive"))
      (node (ref "R8") (pin "2") (pinfunction "2_2") (pintype "passive"))
    )
    (net (code "64") (name "Net-(IC4A-+IN)") (class "Default")
      (node (ref "IC4") (pin "3") (pinfunction "+IN_3") (pintype "input"))
      (node (ref "R19") (pin "1") (pinfunction "1_1") (pintype "passive"))
      (node (ref "R20") (pin "2") (pinfunction "2_2") (pintype "passive"))
      (node (ref "R50") (pin "1") (pinfunction "1_1") (pintype "passive"))
    )
    (net (code "65") (name "Net-(IC4C-+IN)") (class "Default")
      (node (ref "IC4") (pin "10") (pinfunction "+IN_10") (pintype "input"))
      (node (ref "R47") (pin "1") (pinfunction "1_1") (pintype "passive"))
    )
    (net (code "66") (name "Net-(IC4C--IN)") (class "Default")
      (node (ref "IC4") (pin "9") (pinfunction "-IN_9") (pintype "input"))
      (node (ref "R45") (pin "2") (pinfunction "2_2") (pintype "passive"))
      (node (ref "R46") (pin "1") (pinfunction "1_1") (pintype "passive"))
    )
    (net (code "67") (name "Net-(IC4D--IN)") (class "Default")
      (node (ref "IC4") (pin "13") (pinfunction "-IN_13") (pintype "input"))
      (node (ref "IC4") (pin "14") (pinfunction "OUT_14") (pintype "output"))
    )
    (net (code "68") (name "Net-(J7-GND)") (class "Default")
      (node (ref "J4") (pin "2") (pinfunction "2_2") (pintype "passive"))
      (node (ref "J7") (pin "P$4") (pinfunction "GND_P$4") (pintype "bidirectional"))
    )
    (net (code "69") (name "Net-(J7-PWR)") (class "Default")
      (node (ref "J4") (pin "1") (pinfunction "1_1") (pintype "passive"))
      (node (ref "J7") (pin "VIN0") (pinfunction "PWR_VIN0") (pintype "bidirectional"))
      (node (ref "S1") (pin "3") (pinfunction "S_3") (pintype "passive"))
    )
    (net (code "70") (name "Net-(P1-S)") (class "Default")
      (node (ref "P1") (pin "P$2") (pinfunction "S_P$2") (pintype "passive"))
      (node (ref "R18") (pin "1") (pinfunction "1_1") (pintype "passive"))
    )
    (net (code "71") (name "Net-(P2-A)") (class "Default")
      (node (ref "P2") (pin "P$3") (pinfunction "A_P$3") (pintype "passive"))
      (node (ref "S6") (pin "2") (pinfunction "P_2") (pintype "passive"))
    )
    (net (code "72") (name "Net-(P2-S)") (class "Default")
      (node (ref "P2") (pin "P$2") (pinfunction "S_P$2") (pintype "passive"))
      (node (ref "R55") (pin "1") (pinfunction "1_1") (pintype "passive"))
    )
    (net (code "73") (name "Net-(P3-A)") (class "Default")
      (node (ref "P3") (pin "P$3") (pinfunction "A_P$3") (pintype "passive"))
      (node (ref "R43") (pin "1") (pinfunction "1_1") (pintype "passive"))
    )
    (net (code "74") (name "Net-(P3-E)") (class "Default")
      (node (ref "P3") (pin "P$1") (pinfunction "E_P$1") (pintype "passive"))
      (node (ref "R41") (pin "2") (pinfunction "2_2") (pintype "passive"))
    )
    (net (code "75") (name "Net-(P3-S)") (class "Default")
      (node (ref "P3") (pin "P$2") (pinfunction "S_P$2") (pintype "passive"))
      (node (ref "R17") (pin "1") (pinfunction "1_1") (pintype "passive"))
    )
    (net (code "76") (name "Net-(P4-A)") (class "Default")
      (node (ref "P4") (pin "P$3") (pinfunction "A_P$3") (pintype "passive"))
      (node (ref "S9") (pin "2") (pinfunction "P_2") (pintype "passive"))
    )
    (net (code "77") (name "Net-(P6-S)") (class "Default")
      (node (ref "P6") (pin "P$2") (pinfunction "S_P$2") (pintype "passive"))
      (node (ref "R44") (pin "1") (pinfunction "1_1") (pintype "passive"))
    )
    (net (code "78") (name "Net-(P7-A)") (class "Default")
      (node (ref "P7") (pin "P$3") (pinfunction "A_P$3") (pintype "passive"))
      (node (ref "S7") (pin "2") (pinfunction "P_2") (pintype "passive"))
    )
    (net (code "79") (name "Net-(P7-S)") (class "Default")
      (node (ref "P7") (pin "P$2") (pinfunction "S_P$2") (pintype "passive"))
      (node (ref "R28") (pin "1") (pinfunction "1_1") (pintype "passive"))
    )
    (net (code "80") (name "Net-(P8-A)") (class "Default")
      (node (ref "P8") (pin "P$3") (pinfunction "A_P$3") (pintype "passive"))
      (node (ref "S8") (pin "2") (pinfunction "P_2") (pintype "passive"))
    )
    (net (code "81") (name "Net-(P8-S)") (class "Default")
      (node (ref "P8") (pin "P$2") (pinfunction "S_P$2") (pintype "passive"))
      (node (ref "R22") (pin "1") (pinfunction "1_1") (pintype "passive"))
    )
    (net (code "82") (name "Net-(P10-E)") (class "Default")
      (node (ref "D1") (pin "C") (pinfunction "C_C") (pintype "passive"))
      (node (ref "P10") (pin "P$1") (pinfunction "E_P$1") (pintype "passive"))
    )
    (net (code "83") (name "Net-(P11-E)") (class "Default")
      (node (ref "D2") (pin "A") (pinfunction "A_A") (pintype "passive"))
      (node (ref "P11") (pin "P$1") (pinfunction "E_P$1") (pintype "passive"))
    )
    (net (code "84") (name "Net-(P12-A)") (class "Default")
      (node (ref "P12") (pin "P$3") (pinfunction "A_P$3") (pintype "passive"))
      (node (ref "R52") (pin "1") (pinfunction "1_1") (pintype "passive"))
    )
    (net (code "85") (name "Net-(Q2-B)") (class "Default")
      (node (ref "Q2") (pin "1") (pinfunction "B_1") (pintype "passive"))
      (node (ref "R6") (pin "1") (pinfunction "1_1") (pintype "passive"))
      (node (ref "R7") (pin "2") (pinfunction "2_2") (pintype "passive"))
    )
    (net (code "86") (name "Net-(Q4-B)") (class "Default")
      (node (ref "Q4") (pin "1") (pinfunction "B_1") (pintype "passive"))
      (node (ref "R10") (pin "1") (pinfunction "1_1") (pintype "passive"))
    )
    (net (code "87") (name "Net-(Q5-B)") (class "Default")
      (node (ref "Q5") (pin "1") (pinfunction "B_1") (pintype "passive"))
      (node (ref "R38") (pin "2") (pinfunction "2_2") (pintype "passive"))
    )
    (net (code "88") (name "Net-(S2-S)") (class "Default")
      (node (ref "R35") (pin "1") (pinfunction "1_1") (pintype "passive"))
      (node (ref "S2") (pin "3") (pinfunction "S_3") (pintype "passive"))
    )
    (net (code "89") (name "Net-(S5-O)") (class "Default")
      (node (ref "R32") (pin "1") (pinfunction "1_1") (pintype "passive"))
      (node (ref "S5") (pin "1") (pinfunction "O_1") (pintype "passive"))
    )
    (net (code "90") (name "Net-(S10-P)") (class "Default")
      (node (ref "S10") (pin "2") (pinfunction "P_2") (pintype "passive"))
      (node (ref "S8") (pin "1") (pinfunction "O_1") (pintype "passive"))
    )
    (net (code "91") (name "Net-(S11-P)") (class "Default")
      (node (ref "S11") (pin "2") (pinfunction "P_2") (pintype "passive"))
      (node (ref "S7") (pin "1") (pinfunction "O_1") (pintype "passive"))
    )
    (net (code "92") (name "unconnected-(CN2-P$3-Pad5)") (class "Default")
      (node (ref "CN2") (pin "5") (pinfunction "P$3_5") (pintype "bidirectional"))
    )
    (net (code "93") (name "unconnected-(CN3-P$2-Pad3)") (class "Default")
      (node (ref "CN3") (pin "3") (pinfunction "P$2_3") (pintype "bidirectional"))
    )
    (net (code "94") (name "unconnected-(CN3-P$3-Pad5)") (class "Default")
      (node (ref "CN3") (pin "5") (pinfunction "P$3_5") (pintype "bidirectional"))
    )
    (net (code "95") (name "unconnected-(CN3-P$4-Pad4)") (class "Default")
      (node (ref "CN3") (pin "4") (pinfunction "P$4_4") (pintype "bidirectional"))
    )
    (net (code "96") (name "unconnected-(IC5-DIS-Pad7)") (class "Default")
      (node (ref "IC5") (pin "7") (pinfunction "DIS_7") (pintype "input"))
    )
    (net (code "97") (name "unconnected-(IC6-BYPASS-Pad7)") (class "Default")
      (node (ref "IC6") (pin "7") (pinfunction "BYPASS_7") (pintype "passive"))
    )
    (net (code "98") (name "unconnected-(IC6-GAIN-Pad1)") (class "Default")
      (node (ref "IC6") (pin "1") (pinfunction "GAIN_1") (pintype "passive"))
    )
    (net (code "99") (name "unconnected-(IC6-GAIN-Pad8)") (class "Default")
      (node (ref "IC6") (pin "8") (pinfunction "GAIN_8") (pintype "passive"))
    )
    (net (code "100") (name "unconnected-(Q1-C-Pad3)") (class "Default")
      (node (ref "Q1") (pin "3") (pinfunction "C_3") (pintype "passive"))
    )
    (net (code "101") (name "unconnected-(S1-O-Pad1)") (class "Default")
      (node (ref "S1") (pin "1") (pinfunction "O_1") (pintype "passive"))
    )
    (net (code "102") (name "unconnected-(S2-O-Pad1)") (class "Default")
      (node (ref "S2") (pin "1") (pinfunction "O_1") (pintype "passive"))
    )
    (net (code "103") (name "unconnected-(S4-O-Pad1)") (class "Default")
      (node (ref "S4") (pin "1") (pinfunction "O_1") (pintype "passive"))
    )
    (net (code "104") (name "unconnected-(S5-S-Pad3)") (class "Default")
      (node (ref "S5") (pin "3") (pinfunction "S_3") (pintype "passive"))
    )
  )
)
